# Regensensor.net
KiCad netlist of a schematic drawn in EAGLE
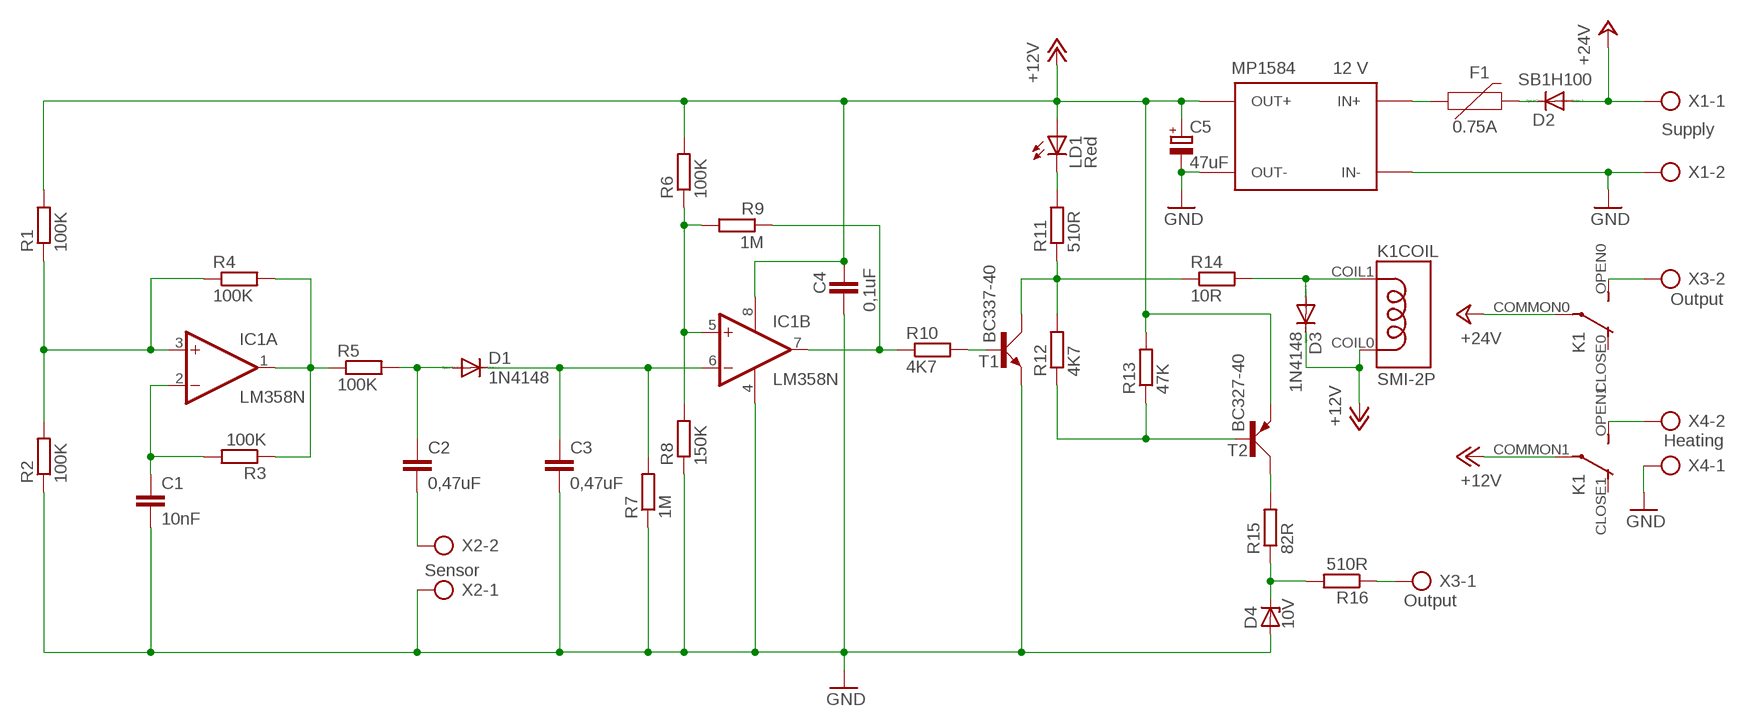
[diagram p0: schematic, sheet 1]

(export (version "E")
  (design (tool "Eeschema 10.0.6"))
  (components
    (comp (ref "C1")
      (value "10nF")
      (footprint "eagle-import:C050-055X075")
      (libsource (lib "eagle-import") (part "C-EU050-055X075"))
    )
    (comp (ref "C2")
      (value "0,47uF")
      (footprint "eagle-import:C050-035X075")
      (libsource (lib "eagle-import") (part "C-EU050-035X075"))
    )
    (comp (ref "C3")
      (value "0,47uF")
      (footprint "eagle-import:C050-035X075")
      (libsource (lib "eagle-import") (part "C-EU050-035X075"))
    )
    (comp (ref "C4")
      (value "0,1uF")
      (footprint "eagle-import:C025-030X050")
      (libsource (lib "eagle-import") (part "C-EU025-030X050"))
    )
    (comp (ref "C5")
      (value "47uF")
      (footprint "eagle-import:E5-6")
      (libsource (lib "eagle-import") (part "CPOL-EUE5-6"))
    )
    (comp (ref "D1")
      (value "1N4148")
      (footprint "eagle-import:DO35-2V")
      (libsource (lib "eagle-import") (part "1N4148DO35-2V"))
    )
    (comp (ref "D2")
      (value "SB1H100")
      (footprint "eagle-import:DO41-7.6")
      (libsource (lib "eagle-import") (part "DIODE-DO41-7.6"))
    )
    (comp (ref "D3")
      (value "1N4148")
      (footprint "eagle-import:DO35-7")
      (libsource (lib "eagle-import") (part "1N4148DO35-7"))
    )
    (comp (ref "D4")
      (value "10V")
      (footprint "eagle-import:ZDIO-2.5")
      (libsource (lib "eagle-import") (part "ZENER-DIODEZD-2.5"))
    )
    (comp (ref "F1")
      (value "0.75A")
      (footprint "eagle-import:RGEF250")
      (libsource (lib "eagle-import") (part "PPTCRGEF250"))
    )
    (comp (ref "IC1")
      (value "LM358N")
      (footprint "eagle-import:DIL08")
      (libsource (lib "eagle-import") (part "LM358N"))
    )
    (comp (ref "K1")
      (value "SMI-2P")
      (footprint "eagle-import:SMI")
      (libsource (lib "eagle-import") (part "SMI-2P"))
    )
    (comp (ref "LD1")
      (value "Red")
      (footprint "eagle-import:LED5MM")
      (libsource (lib "eagle-import") (part "LED5MM"))
    )
    (comp (ref "MP1584")
      (value "12 V")
      (footprint "eagle-import:MP1584")
      (libsource (lib "eagle-import") (part "DC-DC-STEP-DOWNMP1584"))
    )
    (comp (ref "R1")
      (value "100K")
      (footprint "eagle-import:0204V")
      (libsource (lib "eagle-import") (part "R-EU_0204/2V"))
    )
    (comp (ref "R2")
      (value "100K")
      (footprint "eagle-import:0204V")
      (libsource (lib "eagle-import") (part "R-EU_0204/2V"))
    )
    (comp (ref "R3")
      (value "100K")
      (footprint "eagle-import:0204V")
      (libsource (lib "eagle-import") (part "R-EU_0204/2V"))
    )
    (comp (ref "R4")
      (value "100K")
      (footprint "eagle-import:0204_5")
      (libsource (lib "eagle-import") (part "R-EU_0204/5"))
    )
    (comp (ref "R5")
      (value "100K")
      (footprint "eagle-import:0204V")
      (libsource (lib "eagle-import") (part "R-EU_0204/2V"))
    )
    (comp (ref "R6")
      (value "100K")
      (footprint "eagle-import:0204_5")
      (libsource (lib "eagle-import") (part "R-EU_0204/5"))
    )
    (comp (ref "R7")
      (value "1M")
      (footprint "eagle-import:0204V")
      (libsource (lib "eagle-import") (part "R-EU_0204/2V"))
    )
    (comp (ref "R8")
      (value "150K")
      (footprint "eagle-import:0204_5")
      (libsource (lib "eagle-import") (part "R-EU_0204/5"))
    )
    (comp (ref "R9")
      (value "1M")
      (footprint "eagle-import:0204_5")
      (libsource (lib "eagle-import") (part "R-EU_0204/5"))
    )
    (comp (ref "R10")
      (value "4K7")
      (footprint "eagle-import:0204_5")
      (libsource (lib "eagle-import") (part "R-EU_0204/5"))
    )
    (comp (ref "R11")
      (value "510R")
      (footprint "eagle-import:0204V")
      (libsource (lib "eagle-import") (part "R-EU_0204/2V"))
    )
    (comp (ref "R12")
      (value "4K7")
      (footprint "eagle-import:0204V")
      (libsource (lib "eagle-import") (part "R-EU_0204/2V"))
    )
    (comp (ref "R13")
      (value "47K")
      (footprint "eagle-import:0204V")
      (libsource (lib "eagle-import") (part "R-EU_0204/2V"))
    )
    (comp (ref "R14")
      (value "10R")
      (footprint "eagle-import:0204V")
      (libsource (lib "eagle-import") (part "R-EU_0204/2V"))
    )
    (comp (ref "R15")
      (value "82R")
      (footprint "eagle-import:0204V")
      (libsource (lib "eagle-import") (part "R-EU_0204/2V"))
    )
    (comp (ref "R16")
      (value "510R")
      (footprint "eagle-import:0204V")
      (libsource (lib "eagle-import") (part "R-EU_0204/2V"))
    )
    (comp (ref "T1")
      (value "BC337-40")
      (footprint "eagle-import:TO92-LINE")
      (libsource (lib "eagle-import") (part "BC337LINE"))
    )
    (comp (ref "T2")
      (value "BC327-40")
      (footprint "eagle-import:TO92-LINE")
      (libsource (lib "eagle-import") (part "BC327LINE"))
    )
    (comp (ref "X1")
      (value "Supply")
      (footprint "eagle-import:MKDSB-3_2-2")
      (libsource (lib "eagle-import") (part "MKDS-3/25,08"))
    )
    (comp (ref "X2")
      (value "Sensor")
      (footprint "eagle-import:MKDSB-3_2-2")
      (libsource (lib "eagle-import") (part "MKDS-3/25,08"))
    )
    (comp (ref "X3")
      (value "Output")
      (footprint "eagle-import:MKDSB-3_2-2")
      (libsource (lib "eagle-import") (part "MKDS-3/25,08"))
    )
    (comp (ref "X4")
      (value "Heating")
      (footprint "eagle-import:MKDSB-3_2-2")
      (libsource (lib "eagle-import") (part "MKDS-3/25,08"))
    )
  )
  (nets
    (net (code "1") (name "+12V") (class "Default")
      (node (ref "C4") (pin "1") (pinfunction "1_1") (pintype "passive"))
      (node (ref "C5") (pin "+") (pinfunction "+_+") (pintype "passive"))
      (node (ref "D3") (pin "C") (pinfunction "C_C") (pintype "passive"))
      (node (ref "IC1") (pin "8") (pinfunction "V+_8") (pintype "power_in"))
      (node (ref "K1") (pin "COIL0") (pinfunction "0_COIL0") (pintype "passive"))
      (node (ref "K1") (pin "COMMON1") (pinfunction "COMMON_COMMON1") (pintype "passive"))
      (node (ref "LD1") (pin "A") (pinfunction "A_A") (pintype "passive"))
      (node (ref "MP1584") (pin "OUT+0") (pinfunction "OUT+_OUT+0") (pintype "power_in"))
      (node (ref "MP1584") (pin "OUT+1") (pinfunction "OUT+_OUT+1") (pintype "power_in"))
      (node (ref "R1") (pin "2") (pinfunction "2_2") (pintype "passive"))
      (node (ref "R13") (pin "2") (pinfunction "2_2") (pintype "passive"))
      (node (ref "R6") (pin "2") (pinfunction "2_2") (pintype "passive"))
      (node (ref "T2") (pin "1") (pinfunction "E_1") (pintype "passive"))
    )
    (net (code "2") (name "+24V") (class "Default")
      (node (ref "D2") (pin "A") (pinfunction "A_A") (pintype "passive"))
      (node (ref "K1") (pin "COMMON0") (pinfunction "COMMON_COMMON0") (pintype "passive"))
      (node (ref "X1") (pin "1") (pinfunction "KL_1") (pintype "passive"))
    )
    (net (code "3") (name "GND") (class "Default")
      (node (ref "C1") (pin "2") (pinfunction "2_2") (pintype "passive"))
      (node (ref "C3") (pin "2") (pinfunction "2_2") (pintype "passive"))
      (node (ref "C4") (pin "2") (pinfunction "2_2") (pintype "passive"))
      (node (ref "C5") (pin "-") (pinfunction "-_-") (pintype "passive"))
      (node (ref "D4") (pin "A") (pinfunction "A_A") (pintype "passive"))
      (node (ref "IC1") (pin "4") (pinfunction "V-_4") (pintype "power_in"))
      (node (ref "MP1584") (pin "IN-0") (pinfunction "IN-_IN-0") (pintype "power_in"))
      (node (ref "MP1584") (pin "IN-1") (pinfunction "IN-_IN-1") (pintype "power_in"))
      (node (ref "MP1584") (pin "OUT-0") (pinfunction "OUT-_OUT-0") (pintype "power_in"))
      (node (ref "MP1584") (pin "OUT-1") (pinfunction "OUT-_OUT-1") (pintype "power_in"))
      (node (ref "R2") (pin "1") (pinfunction "1_1") (pintype "passive"))
      (node (ref "R7") (pin "1") (pinfunction "1_1") (pintype "passive"))
      (node (ref "R8") (pin "1") (pinfunction "1_1") (pintype "passive"))
      (node (ref "T1") (pin "1") (pinfunction "E_1") (pintype "passive"))
      (node (ref "X1") (pin "2") (pinfunction "KL_2") (pintype "passive"))
      (node (ref "X2") (pin "1") (pinfunction "KL_1") (pintype "passive"))
      (node (ref "X4") (pin "1") (pinfunction "KL_1") (pintype "passive"))
    )
    (net (code "4") (name "Net-(C2-Pad1)") (class "Default")
      (node (ref "C2") (pin "1") (pinfunction "1_1") (pintype "passive"))
      (node (ref "D1") (pin "A") (pinfunction "A_A") (pintype "passive"))
      (node (ref "R5") (pin "2") (pinfunction "2_2") (pintype "passive"))
    )
    (net (code "5") (name "Net-(D4-PadC)") (class "Default")
      (node (ref "D4") (pin "C") (pinfunction "C_C") (pintype "passive"))
      (node (ref "R15") (pin "1") (pinfunction "1_1") (pintype "passive"))
      (node (ref "R16") (pin "2") (pinfunction "2_2") (pintype "passive"))
    )
    (net (code "6") (name "Net-(F1-1)") (class "Default")
      (node (ref "F1") (pin "P$1") (pinfunction "1_P$1") (pintype "bidirectional"))
      (node (ref "MP1584") (pin "IN+0") (pinfunction "IN+_IN+0") (pintype "power_in"))
      (node (ref "MP1584") (pin "IN+1") (pinfunction "IN+_IN+1") (pintype "power_in"))
    )
    (net (code "7") (name "Net-(F1-2)") (class "Default")
      (node (ref "D2") (pin "C") (pinfunction "C_C") (pintype "passive"))
      (node (ref "F1") (pin "P$2") (pinfunction "2_P$2") (pintype "bidirectional"))
    )
    (net (code "8") (name "Net-(IC1A-+IN)") (class "Default")
      (node (ref "IC1") (pin "3") (pinfunction "+IN_3") (pintype "input"))
      (node (ref "R1") (pin "1") (pinfunction "1_1") (pintype "passive"))
      (node (ref "R2") (pin "2") (pinfunction "2_2") (pintype "passive"))
      (node (ref "R4") (pin "1") (pinfunction "1_1") (pintype "passive"))
    )
    (net (code "9") (name "Net-(IC1A--IN)") (class "Default")
      (node (ref "C1") (pin "1") (pinfunction "1_1") (pintype "passive"))
      (node (ref "IC1") (pin "2") (pinfunction "-IN_2") (pintype "input"))
      (node (ref "R3") (pin "2") (pinfunction "2_2") (pintype "passive"))
    )
    (net (code "10") (name "Net-(IC1A-OUT)") (class "Default")
      (node (ref "IC1") (pin "1") (pinfunction "OUT_1") (pintype "output"))
      (node (ref "R3") (pin "1") (pinfunction "1_1") (pintype "passive"))
      (node (ref "R4") (pin "2") (pinfunction "2_2") (pintype "passive"))
      (node (ref "R5") (pin "1") (pinfunction "1_1") (pintype "passive"))
    )
    (net (code "11") (name "Net-(IC1B-+IN)") (class "Default")
      (node (ref "IC1") (pin "5") (pinfunction "+IN_5") (pintype "input"))
      (node (ref "R6") (pin "1") (pinfunction "1_1") (pintype "passive"))
      (node (ref "R8") (pin "2") (pinfunction "2_2") (pintype "passive"))
      (node (ref "R9") (pin "2") (pinfunction "2_2") (pintype "passive"))
    )
    (net (code "12") (name "Net-(IC1B--IN)") (class "Default")
      (node (ref "C3") (pin "1") (pinfunction "1_1") (pintype "passive"))
      (node (ref "D1") (pin "C") (pinfunction "C_C") (pintype "passive"))
      (node (ref "IC1") (pin "6") (pinfunction "-IN_6") (pintype "input"))
      (node (ref "R7") (pin "2") (pinfunction "2_2") (pintype "passive"))
    )
    (net (code "13") (name "Net-(IC1B-OUT)") (class "Default")
      (node (ref "IC1") (pin "7") (pinfunction "OUT_7") (pintype "output"))
      (node (ref "R10") (pin "1") (pinfunction "1_1") (pintype "passive"))
      (node (ref "R9") (pin "1") (pinfunction "1_1") (pintype "passive"))
    )
    (net (code "14") (name "Net-(K1A-1)") (class "Default")
      (node (ref "D3") (pin "A") (pinfunction "A_A") (pintype "passive"))
      (node (ref "K1") (pin "COIL1") (pinfunction "1_COIL1") (pintype "passive"))
      (node (ref "R14") (pin "2") (pinfunction "2_2") (pintype "passive"))
    )
    (net (code "15") (name "Net-(K1B-OPEN)") (class "Default")
      (node (ref "K1") (pin "OPEN0") (pinfunction "OPEN_OPEN0") (pintype "passive"))
      (node (ref "X3") (pin "2") (pinfunction "KL_2") (pintype "passive"))
    )
    (net (code "16") (name "Net-(K1C-OPEN)") (class "Default")
      (node (ref "K1") (pin "OPEN1") (pinfunction "OPEN_OPEN1") (pintype "passive"))
      (node (ref "X4") (pin "2") (pinfunction "KL_2") (pintype "passive"))
    )
    (net (code "17") (name "Net-(LD1-C)") (class "Default")
      (node (ref "LD1") (pin "K") (pinfunction "C_K") (pintype "passive"))
      (node (ref "R11") (pin "2") (pinfunction "2_2") (pintype "passive"))
    )
    (net (code "18") (name "Net-(T1-B)") (class "Default")
      (node (ref "R10") (pin "2") (pinfunction "2_2") (pintype "passive"))
      (node (ref "T1") (pin "2") (pinfunction "B_2") (pintype "passive"))
    )
    (net (code "19") (name "Net-(T1-C)") (class "Default")
      (node (ref "R11") (pin "1") (pinfunction "1_1") (pintype "passive"))
      (node (ref "R12") (pin "2") (pinfunction "2_2") (pintype "passive"))
      (node (ref "R14") (pin "1") (pinfunction "1_1") (pintype "passive"))
      (node (ref "T1") (pin "3") (pinfunction "C_3") (pintype "passive"))
    )
    (net (code "20") (name "Net-(T2-B)") (class "Default")
      (node (ref "R12") (pin "1") (pinfunction "1_1") (pintype "passive"))
      (node (ref "R13") (pin "1") (pinfunction "1_1") (pintype "passive"))
      (node (ref "T2") (pin "2") (pinfunction "B_2") (pintype "passive"))
    )
    (net (code "21") (name "Net-(T2-C)") (class "Default")
      (node (ref "R15") (pin "2") (pinfunction "2_2") (pintype "passive"))
      (node (ref "T2") (pin "3") (pinfunction "C_3") (pintype "passive"))
    )
    (net (code "22") (name "Net-(X2B-KL)") (class "Default")
      (node (ref "C2") (pin "2") (pinfunction "2_2") (pintype "passive"))
      (node (ref "X2") (pin "2") (pinfunction "KL_2") (pintype "passive"))
    )
    (net (code "23") (name "Net-(X3A-KL)") (class "Default")
      (node (ref "R16") (pin "1") (pinfunction "1_1") (pintype "passive"))
      (node (ref "X3") (pin "1") (pinfunction "KL_1") (pintype "passive"))
    )
    (net (code "24") (name "unconnected-(K1B-CLOSE-PadCLOSE0)") (class "Default")
      (node (ref "K1") (pin "CLOSE0") (pinfunction "CLOSE_CLOSE0") (pintype "passive"))
    )
    (net (code "25") (name "unconnected-(K1C-CLOSE-PadCLOSE1)") (class "Default")
      (node (ref "K1") (pin "CLOSE1") (pinfunction "CLOSE_CLOSE1") (pintype "passive"))
    )
  )
)
